# Power_Low_V.net
KiCad netlist of a schematic drawn in Altium Designer
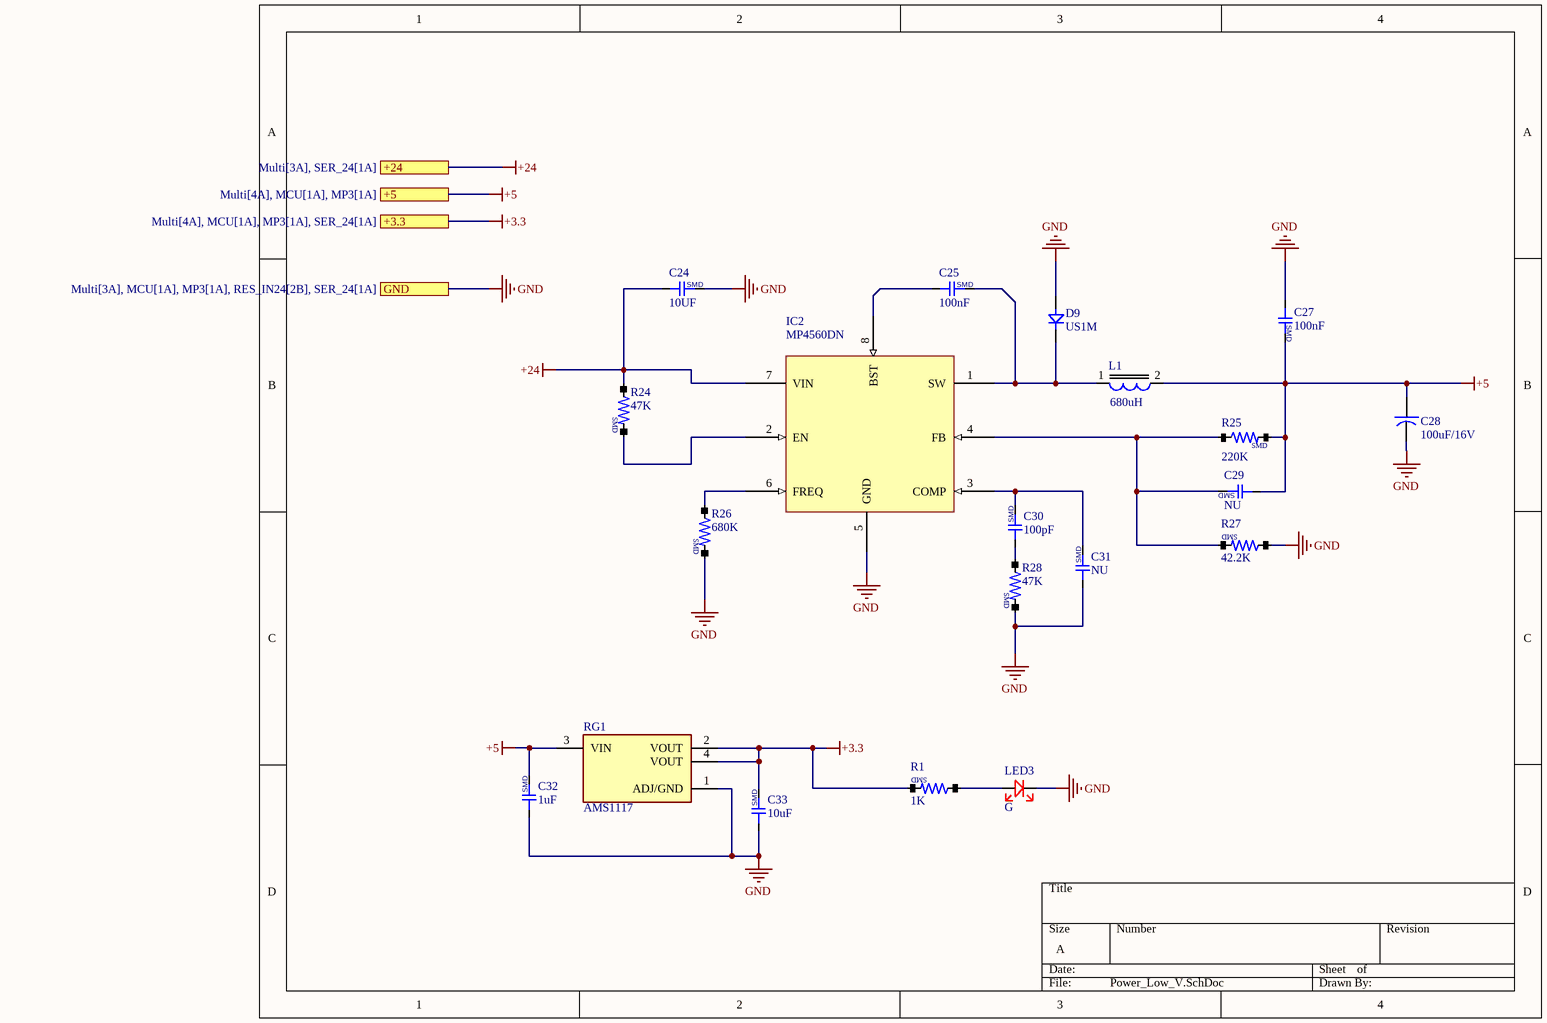
[diagram p0: Power_Low_V.SchDoc]

(export (version "E")
  (design (tool "Eeschema 10.0.6"))
  (components
    (comp (ref "C24") (value "10UF") (footprint "CAP-1206") (libsource (lib "kave-eng-pro") (part "cap_smd")))
    (comp (ref "C25")
      (value "100nF")
      (footprint "CAP-0603")
      (libsource (lib "kave-eng-pro") (part "cap_smd"))
    )
    (comp (ref "C27")
      (value "100nF")
      (footprint "CAP-0603")
      (libsource (lib "kave-eng-pro") (part "cap_smd"))
    )
    (comp (ref "C28")
      (value "100uF/16V")
      (footprint "CAP-EL-P100mil")
      (libsource (lib "kave-eng-pro") (part "cap-electrolit"))
    )
    (comp (ref "C29") (value "NU") (footprint "CAP-0603") (libsource (lib "kave-eng-pro") (part "cap_smd")))
    (comp (ref "C30")
      (value "100pF")
      (footprint "CAP-0603")
      (libsource (lib "kave-eng-pro") (part "cap_smd"))
    )
    (comp (ref "C31") (value "NU") (footprint "CAP-0603") (libsource (lib "kave-eng-pro") (part "cap_smd")))
    (comp (ref "C32") (value "1uF") (footprint "CAP-0805") (libsource (lib "") (part "cap_smd_1")))
    (comp (ref "C33") (value "10uF") (footprint "CAP-0805") (libsource (lib "") (part "cap_smd_1")))
    (comp (ref "D9")
      (value "US1M")
      (footprint "DIOD/1N4007/SMD")
      (libsource (lib "kave-eng-pro") (part "DIOD/RECTIFIERS"))
    )
    (comp (ref "IC2")
      (value "MP4560DN")
      (footprint "SOP8_HIT")
      (libsource (lib "kave-eng-pro") (part "MP4560DN"))
    )
    (comp (ref "L1")
      (value "680uH")
      (footprint "NR6028T680")
      (libsource (lib "kave-eng-pro") (part "inductor"))
    )
    (comp (ref "LED3")
      (value "G")
      (footprint "LED/0805")
      (libsource (lib "kave-eng-pro") (part "LED-1COLER"))
    )
    (comp (ref "R1") (value "1K") (footprint "RES/0603") (libsource (lib "") (part "RES/SMD_1")))
    (comp (ref "R24") (value "47K") (footprint "RES/0603") (libsource (lib "kave-eng-pro") (part "RES/SMD")))
    (comp (ref "R25") (value "220K") (footprint "RES/0603") (libsource (lib "") (part "RES/SMD_2")))
    (comp (ref "R26") (value "680K") (footprint "RES/0805") (libsource (lib "kave-eng-pro") (part "RES/SMD")))
    (comp (ref "R27") (value "42.2K") (footprint "RES/0603") (libsource (lib "") (part "RES/SMD_1")))
    (comp (ref "R28") (value "47K") (footprint "RES/0603") (libsource (lib "kave-eng-pro") (part "RES/SMD")))
    (comp (ref "RG1")
      (value "AMS1117")
      (footprint "AMS1117")
      (libsource (lib "kave-eng-pro") (part "AMS1117"))
    )
  )
  (nets
    (net (code "1") (name "+3.3") (class "Default")
      (node (ref "C33") (pin "2") (pintype "passive"))
      (node (ref "R1") (pin "2") (pinfunction "2_2") (pintype "passive"))
      (node (ref "RG1") (pin "2") (pinfunction "VOUT_2") (pintype "power_in"))
      (node (ref "RG1") (pin "4") (pinfunction "VOUT_4") (pintype "power_in"))
    )
    (net (code "2") (name "+5") (class "Default")
      (node (ref "C27") (pin "2") (pintype "passive"))
      (node (ref "C28") (pin "+") (pintype "passive"))
      (node (ref "C29") (pin "1") (pintype "passive"))
      (node (ref "C32") (pin "2") (pintype "passive"))
      (node (ref "L1") (pin "2") (pintype "passive"))
      (node (ref "R25") (pin "2") (pinfunction "2_2") (pintype "passive"))
      (node (ref "RG1") (pin "3") (pinfunction "VIN_3") (pintype "power_in"))
    )
    (net (code "3") (name "+24") (class "Default")
      (node (ref "C24") (pin "1") (pintype "passive"))
      (node (ref "IC2") (pin "7") (pinfunction "VIN_7") (pintype "power_in"))
      (node (ref "R24") (pin "1") (pinfunction "1_1") (pintype "passive"))
    )
    (net (code "4") (name "GND") (class "Default")
      (node (ref "C24") (pin "2") (pintype "passive"))
      (node (ref "C27") (pin "1") (pintype "passive"))
      (node (ref "C28") (pin "-") (pintype "passive"))
      (node (ref "C31") (pin "1") (pintype "passive"))
      (node (ref "C32") (pin "1") (pintype "passive"))
      (node (ref "C33") (pin "1") (pintype "passive"))
      (node (ref "D9") (pin "A") (pintype "passive"))
      (node (ref "IC2") (pin "5") (pinfunction "GND_5") (pintype "power_in"))
      (node (ref "LED3") (pin "K") (pintype "passive"))
      (node (ref "R26") (pin "2") (pinfunction "2_2") (pintype "passive"))
      (node (ref "R27") (pin "1") (pinfunction "1_1") (pintype "passive"))
      (node (ref "R28") (pin "2") (pinfunction "2_2") (pintype "passive"))
      (node (ref "RG1") (pin "1") (pinfunction "ADJ/GND_1") (pintype "power_in"))
    )
    (net (code "5") (name "Net-(C30-Pad1)") (class "Default")
      (node (ref "C30") (pin "1") (pintype "passive"))
      (node (ref "R28") (pin "1") (pinfunction "1_1") (pintype "passive"))
    )
    (net (code "6") (name "Net-(IC2-BST)") (class "Default")
      (node (ref "C25") (pin "1") (pintype "passive"))
      (node (ref "IC2") (pin "8") (pinfunction "BST_8") (pintype "input"))
    )
    (net (code "7") (name "Net-(IC2-COMP)") (class "Default")
      (node (ref "C30") (pin "2") (pintype "passive"))
      (node (ref "C31") (pin "2") (pintype "passive"))
      (node (ref "IC2") (pin "3") (pinfunction "COMP_3") (pintype "input"))
    )
    (net (code "8") (name "Net-(IC2-EN)") (class "Default")
      (node (ref "IC2") (pin "2") (pinfunction "EN_2") (pintype "input"))
      (node (ref "R24") (pin "2") (pinfunction "2_2") (pintype "passive"))
    )
    (net (code "9") (name "Net-(IC2-FB)") (class "Default")
      (node (ref "C29") (pin "2") (pintype "passive"))
      (node (ref "IC2") (pin "4") (pinfunction "FB_4") (pintype "input"))
      (node (ref "R25") (pin "1") (pinfunction "1_1") (pintype "passive"))
      (node (ref "R27") (pin "2") (pinfunction "2_2") (pintype "passive"))
    )
    (net (code "10") (name "Net-(IC2-FREQ)") (class "Default")
      (node (ref "IC2") (pin "6") (pinfunction "FREQ_6") (pintype "input"))
      (node (ref "R26") (pin "1") (pinfunction "1_1") (pintype "passive"))
    )
    (net (code "11") (name "Net-(IC2-SW)") (class "Default")
      (node (ref "C25") (pin "2") (pintype "passive"))
      (node (ref "D9") (pin "K") (pintype "passive"))
      (node (ref "IC2") (pin "1") (pinfunction "SW_1") (pintype "power_in"))
      (node (ref "L1") (pin "1") (pintype "passive"))
    )
    (net (code "12") (name "Net-(LED3-PadA)") (class "Default")
      (node (ref "LED3") (pin "A") (pintype "passive"))
      (node (ref "R1") (pin "1") (pinfunction "1_1") (pintype "passive"))
    )
  )
)
